# pcb_-_vcf_et_etage_sortie_v2.net
KiCad netlist of a schematic drawn in EAGLE
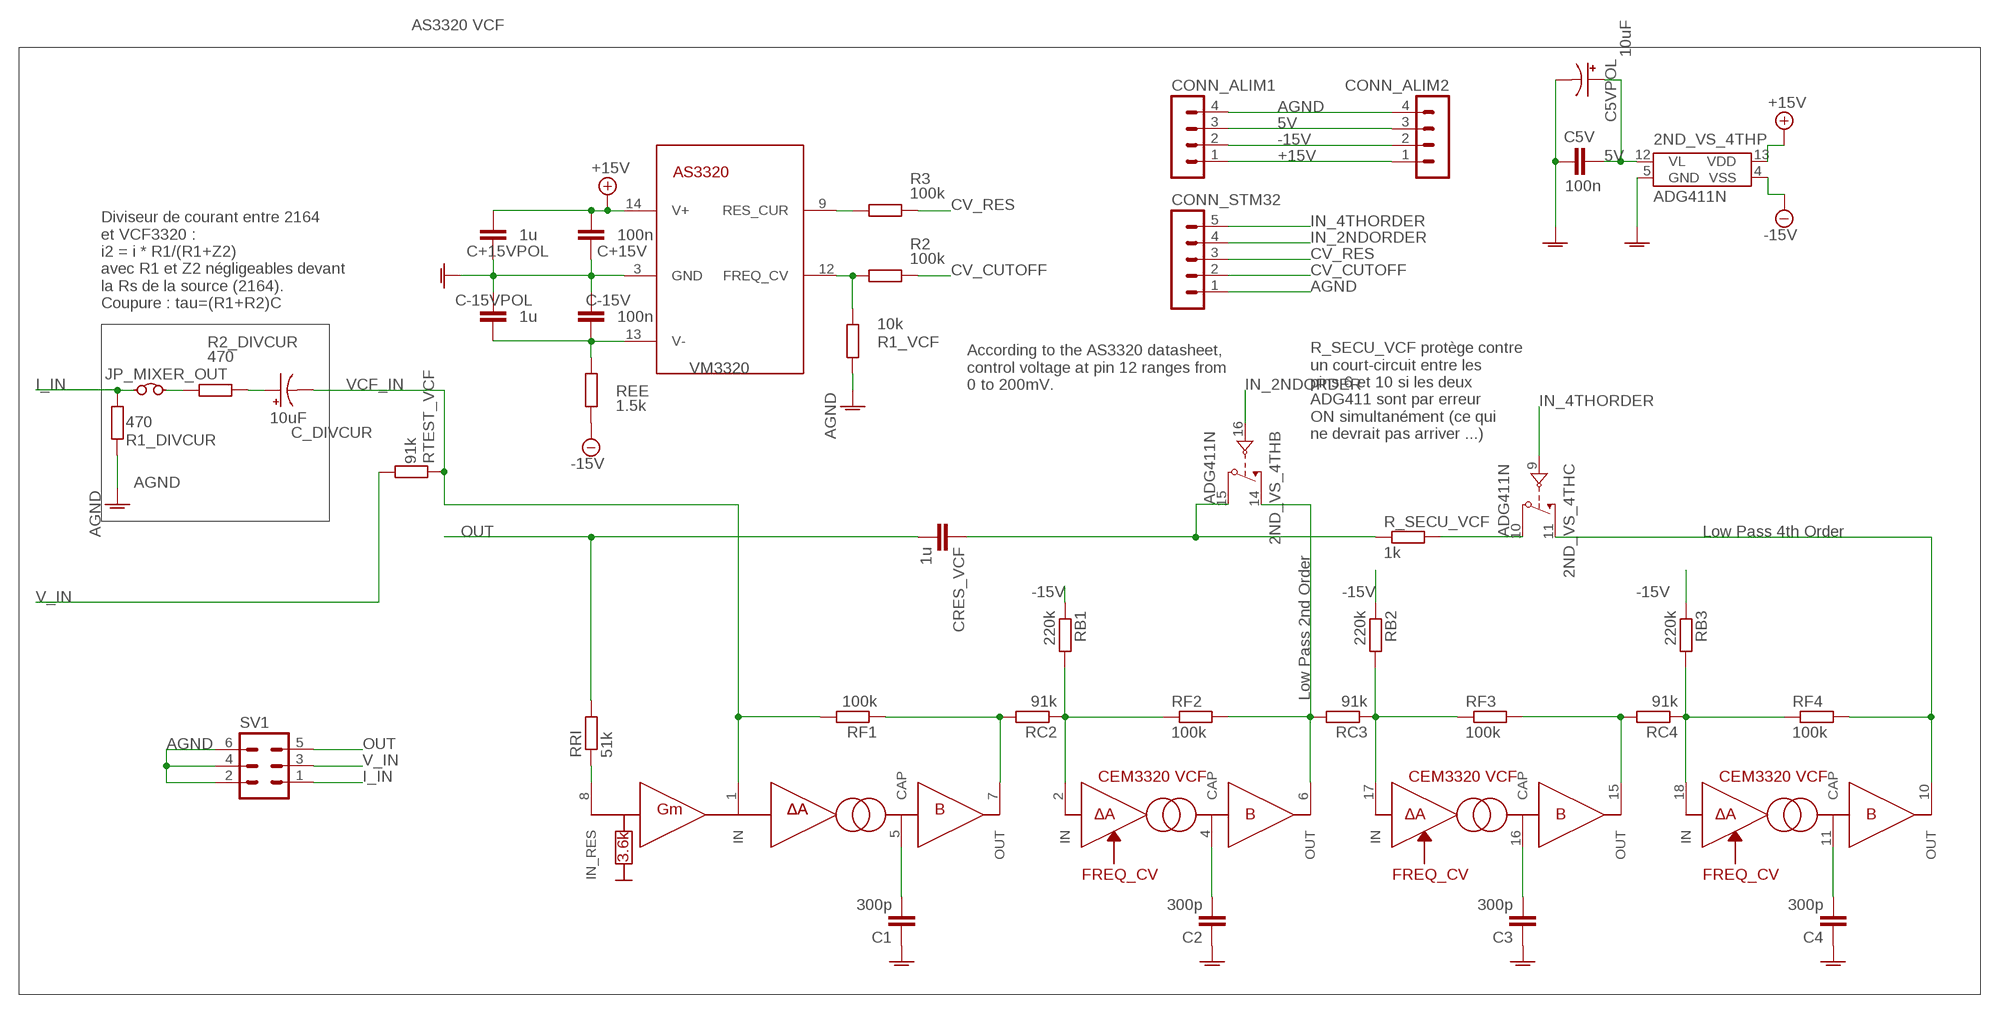
[diagram p0: schematic, sheet 1]

(export (version "E")
  (design (tool "Eeschema 10.0.6"))
  (components
    (comp (ref "2ND_VS_4TH")
      (value "ADG411N")
      (footprint "eagle-import:DIL16")
      (fields (field (name "MF") "ALTERA CORPORATION") (field (name "MPN") "ADG411BN"))
      (libsource (lib "eagle-import") (part "ADG411N"))
    )
    (comp (ref "C+15V")
      (value "100n")
      (footprint "eagle-import:C050-024X044")
      (libsource (lib "eagle-import") (part "C-EU050-024X044"))
    )
    (comp (ref "C+15VPOL")
      (value "1u")
      (footprint "eagle-import:C050-024X044")
      (libsource (lib "eagle-import") (part "C-EU050-024X044"))
    )
    (comp (ref "C-15V")
      (value "100n")
      (footprint "eagle-import:C050-025X075")
      (libsource (lib "eagle-import") (part "C-EU050-025X075"))
    )
    (comp (ref "C-15VPOL")
      (value "1u")
      (footprint "eagle-import:C075-032X103")
      (libsource (lib "eagle-import") (part "C-EU075-032X103"))
    )
    (comp (ref "C1")
      (value "300p")
      (footprint "eagle-import:C050-024X044")
      (libsource (lib "eagle-import") (part "C-EU050-024X044"))
    )
    (comp (ref "C2")
      (value "300p")
      (footprint "eagle-import:C050-024X044")
      (libsource (lib "eagle-import") (part "C-EU050-024X044"))
    )
    (comp (ref "C3")
      (value "300p")
      (footprint "eagle-import:C075-032X103")
      (libsource (lib "eagle-import") (part "C-EU075-032X103"))
    )
    (comp (ref "C4")
      (value "300p")
      (footprint "eagle-import:C075-032X103")
      (libsource (lib "eagle-import") (part "C-EU075-032X103"))
    )
    (comp (ref "C5V")
      (value "100n")
      (footprint "eagle-import:C050-024X044")
      (libsource (lib "eagle-import") (part "C-EU050-024X044"))
    )
    (comp (ref "C5VPOL")
      (value "10uF")
      (footprint "eagle-import:CPOL-RADIAL-2.5MM-5MM-KIT")
      (libsource (lib "eagle-import") (part "10UF-POLAR-RADIAL-2.5MM-KIT-25V-20%"))
    )
    (comp (ref "CONN_ALIM1")
      (value "MA04-1")
      (footprint "eagle-import:MA04-1")
      (libsource (lib "eagle-import") (part "MA04-1"))
    )
    (comp (ref "CONN_ALIM2")
      (value "MA04-1")
      (footprint "eagle-import:MA04-1")
      (libsource (lib "eagle-import") (part "MA04-1"))
    )
    (comp (ref "CONN_STM32")
      (value "MA05-1")
      (footprint "eagle-import:MA05-1")
      (libsource (lib "eagle-import") (part "MA05-1"))
    )
    (comp (ref "CRES_VCF")
      (value "1u")
      (footprint "eagle-import:C075-032X103")
      (libsource (lib "eagle-import") (part "C-EU075-032X103"))
    )
    (comp (ref "C_DIVCUR")
      (value "10uF")
      (footprint "eagle-import:CPOL-RADIAL-2.5MM-5MM-KIT")
      (libsource (lib "eagle-import") (part "10UF-POLAR-RADIAL-2.5MM-KIT-25V-20%"))
    )
    (comp (ref "JP_MIXER_OUT")
      (value "JUMPER_WIRE")
      (footprint "eagle-import:JUMPER")
      (libsource (lib "eagle-import") (part "JUMPER_WIRE"))
    )
    (comp (ref "R1_DIVCUR")
      (value "470")
      (footprint "eagle-import:0207_10")
      (libsource (lib "eagle-import") (part "R-EU_0207/10"))
    )
    (comp (ref "R1_VCF")
      (value "10k")
      (footprint "eagle-import:0204_7")
      (libsource (lib "eagle-import") (part "R-EU_0204/7"))
    )
    (comp (ref "R2")
      (value "100k")
      (footprint "eagle-import:0204_5")
      (libsource (lib "eagle-import") (part "R-EU_0204/5"))
    )
    (comp (ref "R2_DIVCUR")
      (value "470")
      (footprint "eagle-import:0207_10")
      (libsource (lib "eagle-import") (part "R-EU_0207/10"))
    )
    (comp (ref "R3")
      (value "100k")
      (footprint "eagle-import:0204_7")
      (libsource (lib "eagle-import") (part "R-EU_0204/7"))
    )
    (comp (ref "RB1")
      (value "220k")
      (footprint "eagle-import:0207_10")
      (libsource (lib "eagle-import") (part "R-EU_0207/10"))
    )
    (comp (ref "RB2")
      (value "220k")
      (footprint "eagle-import:0204_7")
      (libsource (lib "eagle-import") (part "R-EU_0204/7"))
    )
    (comp (ref "RB3")
      (value "220k")
      (footprint "eagle-import:0204_5")
      (libsource (lib "eagle-import") (part "R-EU_0204/5"))
    )
    (comp (ref "RC2")
      (value "91k")
      (footprint "eagle-import:0204_7")
      (libsource (lib "eagle-import") (part "R-EU_0204/7"))
    )
    (comp (ref "RC3")
      (value "91k")
      (footprint "eagle-import:0204_5")
      (libsource (lib "eagle-import") (part "R-EU_0204/5"))
    )
    (comp (ref "RC4")
      (value "91k")
      (footprint "eagle-import:0204_7")
      (libsource (lib "eagle-import") (part "R-EU_0204/7"))
    )
    (comp (ref "REE")
      (value "1.5k")
      (footprint "eagle-import:0207_10")
      (libsource (lib "eagle-import") (part "R-EU_0207/10"))
    )
    (comp (ref "RF1")
      (value "100k")
      (footprint "eagle-import:0207_10")
      (libsource (lib "eagle-import") (part "R-EU_0207/10"))
    )
    (comp (ref "RF2")
      (value "100k")
      (footprint "eagle-import:0204_5")
      (libsource (lib "eagle-import") (part "R-EU_0204/5"))
    )
    (comp (ref "RF3")
      (value "100k")
      (footprint "eagle-import:0207_10")
      (libsource (lib "eagle-import") (part "R-EU_0207/10"))
    )
    (comp (ref "RF4")
      (value "100k")
      (footprint "eagle-import:0204_7")
      (libsource (lib "eagle-import") (part "R-EU_0204/7"))
    )
    (comp (ref "RRI")
      (value "51k")
      (footprint "eagle-import:0207_10")
      (libsource (lib "eagle-import") (part "R-EU_0207/10"))
    )
    (comp (ref "RTEST_VCF")
      (value "91k")
      (footprint "eagle-import:0204_5")
      (libsource (lib "eagle-import") (part "R-EU_0204/5"))
    )
    (comp (ref "R_SECU_VCF")
      (value "1k")
      (footprint "eagle-import:0204_7")
      (libsource (lib "eagle-import") (part "R-EU_0204/7"))
    )
    (comp (ref "SV1")
      (value "MA03-2")
      (footprint "eagle-import:MA03-2")
      (libsource (lib "eagle-import") (part "MA03-2"))
    )
    (comp (ref "VCF")
      (value "AS3320")
      (footprint "eagle-import:DIL18")
      (libsource (lib "eagle-import") (part "AS3320"))
    )
  )
  (nets
    (net (code "1") (name "+15V") (class "Default")
      (node (ref "2ND_VS_4TH") (pin "13") (pinfunction "VDD_13") (pintype "power_in"))
      (node (ref "C+15V") (pin "2") (pinfunction "2_2") (pintype "passive"))
      (node (ref "C+15VPOL") (pin "2") (pinfunction "2_2") (pintype "passive"))
      (node (ref "CONN_ALIM1") (pin "1") (pinfunction "1_1") (pintype "passive"))
      (node (ref "CONN_ALIM2") (pin "1") (pinfunction "1_1") (pintype "passive"))
      (node (ref "VCF") (pin "14") (pinfunction "V+_14") (pintype "bidirectional"))
    )
    (net (code "2") (name "-15V") (class "Default")
      (node (ref "2ND_VS_4TH") (pin "4") (pinfunction "VSS_4") (pintype "power_in"))
      (node (ref "CONN_ALIM1") (pin "2") (pinfunction "2_2") (pintype "passive"))
      (node (ref "CONN_ALIM2") (pin "2") (pinfunction "2_2") (pintype "passive"))
      (node (ref "RB1") (pin "1") (pinfunction "1_1") (pintype "passive"))
      (node (ref "RB2") (pin "1") (pinfunction "1_1") (pintype "passive"))
      (node (ref "RB3") (pin "1") (pinfunction "1_1") (pintype "passive"))
      (node (ref "REE") (pin "1") (pinfunction "1_1") (pintype "passive"))
    )
    (net (code "3") (name "/5V") (class "Default")
      (node (ref "2ND_VS_4TH") (pin "12") (pinfunction "VL_12") (pintype "power_in"))
      (node (ref "C5V") (pin "1") (pinfunction "1_1") (pintype "passive"))
      (node (ref "C5VPOL") (pin "1") (pinfunction "+_1") (pintype "passive"))
      (node (ref "CONN_ALIM1") (pin "3") (pinfunction "3_3") (pintype "passive"))
      (node (ref "CONN_ALIM2") (pin "3") (pinfunction "3_3") (pintype "passive"))
    )
    (net (code "4") (name "/CV_CUTOFF") (class "Default")
      (node (ref "CONN_STM32") (pin "2") (pinfunction "2_2") (pintype "passive"))
      (node (ref "R2") (pin "2") (pinfunction "2_2") (pintype "passive"))
    )
    (net (code "5") (name "/CV_RES") (class "Default")
      (node (ref "CONN_STM32") (pin "3") (pinfunction "3_3") (pintype "passive"))
      (node (ref "R3") (pin "2") (pinfunction "2_2") (pintype "passive"))
    )
    (net (code "6") (name "/IN_2NDORDER") (class "Default")
      (node (ref "2ND_VS_4TH") (pin "16") (pinfunction "IN_16") (pintype "input"))
      (node (ref "CONN_STM32") (pin "4") (pinfunction "4_4") (pintype "passive"))
    )
    (net (code "7") (name "/IN_4THORDER") (class "Default")
      (node (ref "2ND_VS_4TH") (pin "9") (pinfunction "IN_9") (pintype "input"))
      (node (ref "CONN_STM32") (pin "5") (pinfunction "5_5") (pintype "passive"))
    )
    (net (code "8") (name "/I_IN") (class "Default")
      (node (ref "JP_MIXER_OUT") (pin "1") (pinfunction "1_1") (pintype "passive"))
      (node (ref "R1_DIVCUR") (pin "1") (pinfunction "1_1") (pintype "passive"))
      (node (ref "SV1") (pin "1") (pinfunction "1_1") (pintype "passive"))
    )
    (net (code "9") (name "/OUT") (class "Default")
      (node (ref "CRES_VCF") (pin "2") (pinfunction "2_2") (pintype "passive"))
      (node (ref "RRI") (pin "2") (pinfunction "2_2") (pintype "passive"))
      (node (ref "SV1") (pin "5") (pinfunction "5_5") (pintype "passive"))
    )
    (net (code "10") (name "/VCF_IN") (class "Default")
      (node (ref "C_DIVCUR") (pin "2") (pinfunction "-_2") (pintype "passive"))
      (node (ref "RF1") (pin "2") (pinfunction "2_2") (pintype "passive"))
      (node (ref "RTEST_VCF") (pin "2") (pinfunction "2_2") (pintype "passive"))
      (node (ref "VCF") (pin "1") (pinfunction "IN_1") (pintype "bidirectional"))
    )
    (net (code "11") (name "/VM3320") (class "Default")
      (node (ref "C-15V") (pin "1") (pinfunction "1_1") (pintype "passive"))
      (node (ref "C-15VPOL") (pin "1") (pinfunction "1_1") (pintype "passive"))
      (node (ref "REE") (pin "2") (pinfunction "2_2") (pintype "passive"))
      (node (ref "VCF") (pin "13") (pinfunction "V-_13") (pintype "bidirectional"))
    )
    (net (code "12") (name "/V_IN") (class "Default")
      (node (ref "RTEST_VCF") (pin "1") (pinfunction "1_1") (pintype "passive"))
      (node (ref "SV1") (pin "3") (pinfunction "3_3") (pintype "passive"))
    )
    (net (code "13") (name "AGND") (class "Default")
      (node (ref "2ND_VS_4TH") (pin "5") (pinfunction "GND_5") (pintype "power_in"))
      (node (ref "C+15V") (pin "1") (pinfunction "1_1") (pintype "passive"))
      (node (ref "C+15VPOL") (pin "1") (pinfunction "1_1") (pintype "passive"))
      (node (ref "C-15V") (pin "2") (pinfunction "2_2") (pintype "passive"))
      (node (ref "C-15VPOL") (pin "2") (pinfunction "2_2") (pintype "passive"))
      (node (ref "C1") (pin "1") (pinfunction "1_1") (pintype "passive"))
      (node (ref "C2") (pin "1") (pinfunction "1_1") (pintype "passive"))
      (node (ref "C3") (pin "1") (pinfunction "1_1") (pintype "passive"))
      (node (ref "C4") (pin "1") (pinfunction "1_1") (pintype "passive"))
      (node (ref "C5V") (pin "2") (pinfunction "2_2") (pintype "passive"))
      (node (ref "C5VPOL") (pin "2") (pinfunction "-_2") (pintype "passive"))
      (node (ref "CONN_ALIM1") (pin "4") (pinfunction "4_4") (pintype "passive"))
      (node (ref "CONN_ALIM2") (pin "4") (pinfunction "4_4") (pintype "passive"))
      (node (ref "CONN_STM32") (pin "1") (pinfunction "1_1") (pintype "passive"))
      (node (ref "R1_DIVCUR") (pin "2") (pinfunction "2_2") (pintype "passive"))
      (node (ref "R1_VCF") (pin "2") (pinfunction "2_2") (pintype "passive"))
      (node (ref "SV1") (pin "2") (pinfunction "2_2") (pintype "passive"))
      (node (ref "SV1") (pin "4") (pinfunction "4_4") (pintype "passive"))
      (node (ref "SV1") (pin "6") (pinfunction "6_6") (pintype "passive"))
      (node (ref "VCF") (pin "3") (pinfunction "GND_3") (pintype "bidirectional"))
    )
    (net (code "14") (name "Net-(2ND_VS_4THB-D)") (class "Default")
      (node (ref "2ND_VS_4TH") (pin "15") (pinfunction "D_15") (pintype "passive"))
      (node (ref "CRES_VCF") (pin "1") (pinfunction "1_1") (pintype "passive"))
      (node (ref "R_SECU_VCF") (pin "1") (pinfunction "1_1") (pintype "passive"))
    )
    (net (code "15") (name "Net-(2ND_VS_4THB-S)") (class "Default")
      (node (ref "2ND_VS_4TH") (pin "14") (pinfunction "S_14") (pintype "passive"))
      (node (ref "RC3") (pin "2") (pinfunction "2_2") (pintype "passive"))
      (node (ref "RF2") (pin "2") (pinfunction "2_2") (pintype "passive"))
      (node (ref "VCF") (pin "6") (pinfunction "OUT_6") (pintype "bidirectional"))
    )
    (net (code "16") (name "Net-(2ND_VS_4THC-D)") (class "Default")
      (node (ref "2ND_VS_4TH") (pin "10") (pinfunction "D_10") (pintype "passive"))
      (node (ref "R_SECU_VCF") (pin "2") (pinfunction "2_2") (pintype "passive"))
    )
    (net (code "17") (name "Net-(2ND_VS_4THC-S)") (class "Default")
      (node (ref "2ND_VS_4TH") (pin "11") (pinfunction "S_11") (pintype "passive"))
      (node (ref "RF4") (pin "2") (pinfunction "2_2") (pintype "passive"))
      (node (ref "VCF") (pin "10") (pinfunction "OUT_10") (pintype "bidirectional"))
    )
    (net (code "18") (name "Net-(C_DIVCUR-+)") (class "Default")
      (node (ref "C_DIVCUR") (pin "1") (pinfunction "+_1") (pintype "passive"))
      (node (ref "R2_DIVCUR") (pin "1") (pinfunction "1_1") (pintype "passive"))
    )
    (net (code "19") (name "Net-(JP_MIXER_OUT-Pad2)") (class "Default")
      (node (ref "JP_MIXER_OUT") (pin "2") (pinfunction "2_2") (pintype "passive"))
      (node (ref "R2_DIVCUR") (pin "2") (pinfunction "2_2") (pintype "passive"))
    )
    (net (code "20") (name "Net-(VCFA-CAP)") (class "Default")
      (node (ref "C1") (pin "2") (pinfunction "2_2") (pintype "passive"))
      (node (ref "VCF") (pin "5") (pinfunction "CAP_5") (pintype "bidirectional"))
    )
    (net (code "21") (name "Net-(VCFA-IN_RES)") (class "Default")
      (node (ref "RRI") (pin "1") (pinfunction "1_1") (pintype "passive"))
      (node (ref "VCF") (pin "8") (pinfunction "IN_RES_8") (pintype "bidirectional"))
    )
    (net (code "22") (name "Net-(VCFA-OUT)") (class "Default")
      (node (ref "RC2") (pin "2") (pinfunction "2_2") (pintype "passive"))
      (node (ref "RF1") (pin "1") (pinfunction "1_1") (pintype "passive"))
      (node (ref "VCF") (pin "7") (pinfunction "OUT_7") (pintype "bidirectional"))
    )
    (net (code "23") (name "Net-(VCFB-CAP)") (class "Default")
      (node (ref "C2") (pin "2") (pinfunction "2_2") (pintype "passive"))
      (node (ref "VCF") (pin "4") (pinfunction "CAP_4") (pintype "bidirectional"))
    )
    (net (code "24") (name "Net-(VCFB-IN)") (class "Default")
      (node (ref "RB1") (pin "2") (pinfunction "2_2") (pintype "passive"))
      (node (ref "RC2") (pin "1") (pinfunction "1_1") (pintype "passive"))
      (node (ref "RF2") (pin "1") (pinfunction "1_1") (pintype "passive"))
      (node (ref "VCF") (pin "2") (pinfunction "IN_2") (pintype "bidirectional"))
    )
    (net (code "25") (name "Net-(VCFC-CAP)") (class "Default")
      (node (ref "C4") (pin "2") (pinfunction "2_2") (pintype "passive"))
      (node (ref "VCF") (pin "11") (pinfunction "CAP_11") (pintype "bidirectional"))
    )
    (net (code "26") (name "Net-(VCFC-IN)") (class "Default")
      (node (ref "RB3") (pin "2") (pinfunction "2_2") (pintype "passive"))
      (node (ref "RC4") (pin "1") (pinfunction "1_1") (pintype "passive"))
      (node (ref "RF4") (pin "1") (pinfunction "1_1") (pintype "passive"))
      (node (ref "VCF") (pin "18") (pinfunction "IN_18") (pintype "bidirectional"))
    )
    (net (code "27") (name "Net-(VCFD-CAP)") (class "Default")
      (node (ref "C3") (pin "2") (pinfunction "2_2") (pintype "passive"))
      (node (ref "VCF") (pin "16") (pinfunction "CAP_16") (pintype "bidirectional"))
    )
    (net (code "28") (name "Net-(VCFD-IN)") (class "Default")
      (node (ref "RB2") (pin "2") (pinfunction "2_2") (pintype "passive"))
      (node (ref "RC3") (pin "1") (pinfunction "1_1") (pintype "passive"))
      (node (ref "RF3") (pin "1") (pinfunction "1_1") (pintype "passive"))
      (node (ref "VCF") (pin "17") (pinfunction "IN_17") (pintype "bidirectional"))
    )
    (net (code "29") (name "Net-(VCFD-OUT)") (class "Default")
      (node (ref "RC4") (pin "2") (pinfunction "2_2") (pintype "passive"))
      (node (ref "RF3") (pin "2") (pinfunction "2_2") (pintype "passive"))
      (node (ref "VCF") (pin "15") (pinfunction "OUT_15") (pintype "bidirectional"))
    )
    (net (code "30") (name "Net-(VCFE-FREQ_CV)") (class "Default")
      (node (ref "R1_VCF") (pin "1") (pinfunction "1_1") (pintype "passive"))
      (node (ref "R2") (pin "1") (pinfunction "1_1") (pintype "passive"))
      (node (ref "VCF") (pin "12") (pinfunction "FREQ_CV_12") (pintype "bidirectional"))
    )
    (net (code "31") (name "Net-(VCFE-RES_CUR)") (class "Default")
      (node (ref "R3") (pin "1") (pinfunction "1_1") (pintype "passive"))
      (node (ref "VCF") (pin "9") (pinfunction "RES_CUR_9") (pintype "bidirectional"))
    )
  )
)
